# Viberation.net
KiCad netlist of a schematic drawn in Altium Designer
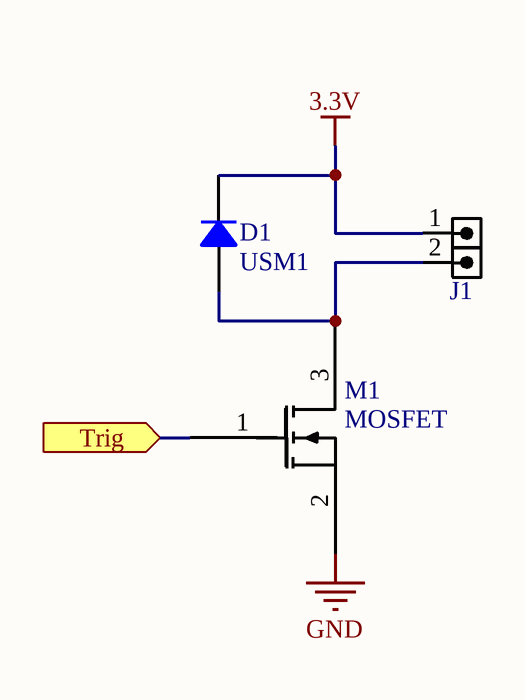
[diagram p0: Viberation.SchDoc]

(export (version "E")
  (design (tool "Eeschema 10.0.6"))
  (components
    (comp (ref "D1")
      (value "USM1")
      (footprint "DO-214AC SMA")
      (description "Diode Standard 1000V 1A Surface Mount SMA")
      (fields (field (name "PARTNUMBER") "US1M-13-F"))
      (libsource (lib "Diode") (part "US1M (SMD SMA)"))
    )
    (comp (ref "J1")
      (value "HDR2")
      (footprint "HDR1SE_M_1X2")
      (description "HEADER, 1mm pitch, test, SMD")
      (libsource (lib "Conn Header") (part "HDRTST_1X2"))
    )
    (comp (ref "M1") (value "MOSFET") (footprint "SOT-23") (libsource (lib "Salman_lib") (part "2N7002A")))
  )
  (nets
    (net (code "1") (name "/Trig") (class "Default") (node (ref "M1") (pin "1") (pintype "passive")))
    (net (code "2") (name "3.3V") (class "Default")
      (node (ref "D1") (pin "2") (pinfunction "2_2") (pintype "passive"))
      (node (ref "J1") (pin "1") (pinfunction "1_1") (pintype "passive"))
    )
    (net (code "3") (name "GND") (class "Default") (node (ref "M1") (pin "2") (pintype "passive")))
    (net (code "4") (name "Net-(D1-Pad1)") (class "Default")
      (node (ref "D1") (pin "1") (pinfunction "1_1") (pintype "passive"))
      (node (ref "J1") (pin "2") (pinfunction "2_2") (pintype "passive"))
      (node (ref "M1") (pin "3") (pintype "passive"))
    )
  )
)
